# alim_2016.net
KiCad netlist of a schematic drawn in EAGLE
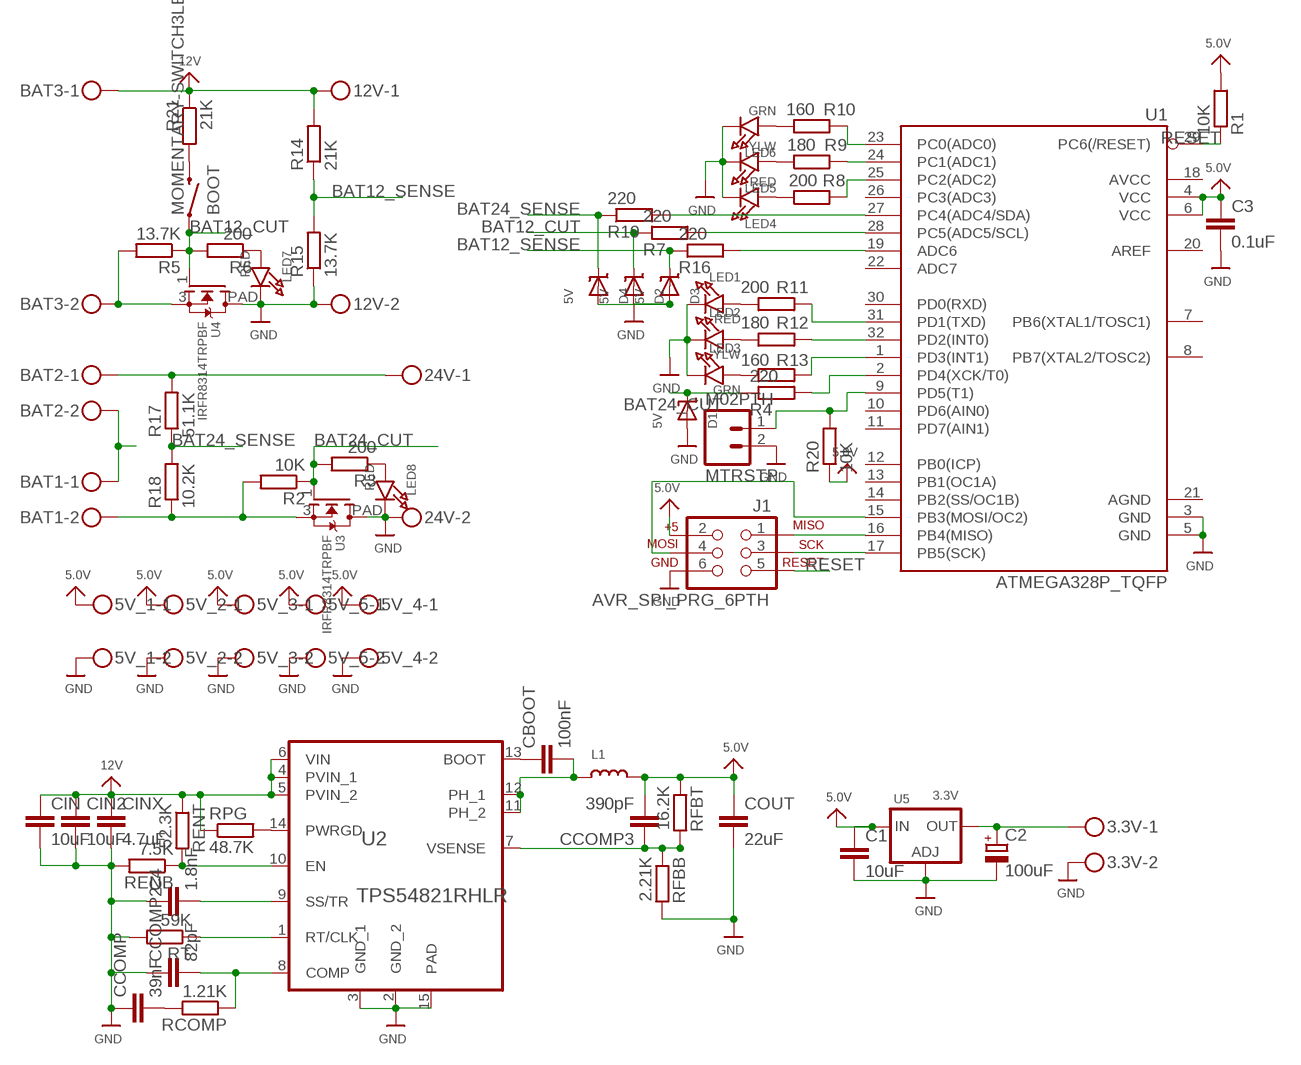
[diagram p0: schematic, sheet 1]

(export (version "E")
  (design (tool "Eeschema 10.0.6"))
  (components
    (comp (ref "3.3V")
      (value "WURTH_2PIN311")
      (footprint "eagle-import:WURTH311")
      (libsource (lib "eagle-import") (part "WURTH_2PIN311"))
    )
    (comp (ref "5V_1")
      (value "WURTH_2PIN311")
      (footprint "eagle-import:WURTH311")
      (libsource (lib "eagle-import") (part "WURTH_2PIN311"))
    )
    (comp (ref "5V_2")
      (value "WURTH_2PIN311")
      (footprint "eagle-import:WURTH311")
      (libsource (lib "eagle-import") (part "WURTH_2PIN311"))
    )
    (comp (ref "5V_3")
      (value "WURTH_2PIN311")
      (footprint "eagle-import:WURTH311")
      (libsource (lib "eagle-import") (part "WURTH_2PIN311"))
    )
    (comp (ref "5V_4")
      (value "WURTH_2PIN311")
      (footprint "eagle-import:WURTH311")
      (libsource (lib "eagle-import") (part "WURTH_2PIN311"))
    )
    (comp (ref "5V_5")
      (value "WURTH_2PIN311")
      (footprint "eagle-import:WURTH311")
      (libsource (lib "eagle-import") (part "WURTH_2PIN311"))
    )
    (comp (ref "12V")
      (value "WURTH_2PIN311")
      (footprint "eagle-import:WURTH311")
      (libsource (lib "eagle-import") (part "WURTH_2PIN311"))
    )
    (comp (ref "24V")
      (value "WURTH_2PIN311")
      (footprint "eagle-import:WURTH311")
      (libsource (lib "eagle-import") (part "WURTH_2PIN311"))
    )
    (comp (ref "BAT1")
      (value "WURTH_2PIN313")
      (footprint "eagle-import:WURTH313_2")
      (libsource (lib "eagle-import") (part "WURTH_2PIN313"))
    )
    (comp (ref "BAT2")
      (value "WURTH_2PIN313")
      (footprint "eagle-import:WURTH313_2")
      (libsource (lib "eagle-import") (part "WURTH_2PIN313"))
    )
    (comp (ref "BAT3")
      (value "WURTH_2PIN313")
      (footprint "eagle-import:WURTH313_2")
      (libsource (lib "eagle-import") (part "WURTH_2PIN313"))
    )
    (comp (ref "BOOT")
      (value "MOMENTARY-SWITCH3LEG")
      (footprint "eagle-import:3LEGGED-TACT")
      (libsource (lib "eagle-import") (part "MOMENTARY-SWITCH3LEG"))
    )
    (comp (ref "C1")
      (value "10uF")
      (footprint "eagle-import:C0805")
      (libsource (lib "eagle-import") (part "C-EUC0805"))
    )
    (comp (ref "C2")
      (value "100uF")
      (footprint "eagle-import:E2,5-7")
      (libsource (lib "eagle-import") (part "CPOL-EUE2.5-7"))
    )
    (comp (ref "C3")
      (value "0.1uF")
      (footprint "eagle-import:C0805")
      (libsource (lib "eagle-import") (part "C-EUC0805"))
    )
    (comp (ref "C4")
      (value "1.8nF")
      (footprint "eagle-import:C0805")
      (libsource (lib "eagle-import") (part "C-EUC0805"))
    )
    (comp (ref "CBOOT")
      (value "100nF")
      (footprint "eagle-import:C0805")
      (libsource (lib "eagle-import") (part "C-EUC0805"))
    )
    (comp (ref "CCOMP")
      (value "39nF")
      (footprint "eagle-import:C0805")
      (libsource (lib "eagle-import") (part "C-EUC0805"))
    )
    (comp (ref "CCOMP2")
      (value "82pF")
      (footprint "eagle-import:C0805")
      (libsource (lib "eagle-import") (part "C-EUC0805"))
    )
    (comp (ref "CCOMP3")
      (value "390pF")
      (footprint "eagle-import:C0805")
      (libsource (lib "eagle-import") (part "C-EUC0805"))
    )
    (comp (ref "CIN")
      (value "10uF")
      (footprint "eagle-import:C0805")
      (libsource (lib "eagle-import") (part "C-EUC0805"))
    )
    (comp (ref "CIN2")
      (value "10uF")
      (footprint "eagle-import:C0805")
      (libsource (lib "eagle-import") (part "C-EUC0805"))
    )
    (comp (ref "CINX")
      (value "4.7uF")
      (footprint "eagle-import:C0805")
      (libsource (lib "eagle-import") (part "C-EUC0805"))
    )
    (comp (ref "COUT")
      (value "22uF")
      (footprint "eagle-import:C0805")
      (libsource (lib "eagle-import") (part "C-EUC0805"))
    )
    (comp (ref "D1")
      (value "5V")
      (footprint "eagle-import:SOD-123")
      (libsource (lib "eagle-import") (part "DIODE-ZENERSOD123"))
    )
    (comp (ref "D2")
      (value "5V")
      (footprint "eagle-import:SOD-123")
      (libsource (lib "eagle-import") (part "DIODE-ZENERSOD123"))
    )
    (comp (ref "D3")
      (value "5V")
      (footprint "eagle-import:SOD-123")
      (libsource (lib "eagle-import") (part "DIODE-ZENERSOD123"))
    )
    (comp (ref "D4")
      (value "5V")
      (footprint "eagle-import:SOD-123")
      (libsource (lib "eagle-import") (part "DIODE-ZENERSOD123"))
    )
    (comp (ref "J1")
      (value "AVR_SPI_PRG_6PTH")
      (footprint "eagle-import:2X3")
      (libsource (lib "eagle-import") (part "AVR_SPI_PRG_6PTH"))
    )
    (comp (ref "L1")
      (value "2.2uH")
      (footprint "eagle-import:XAL5030")
      (libsource (lib "eagle-import") (part "XAL5030"))
    )
    (comp (ref "LED1")
      (value "RED")
      (footprint "eagle-import:CHIPLED_0805_NOOUTLINE")
      (libsource (lib "eagle-import") (part "LED0805_NOOUTLINE"))
    )
    (comp (ref "LED2")
      (value "YLW")
      (footprint "eagle-import:CHIPLED_0805_NOOUTLINE")
      (libsource (lib "eagle-import") (part "LED0805_NOOUTLINE"))
    )
    (comp (ref "LED3")
      (value "GRN")
      (footprint "eagle-import:CHIPLED_0805_NOOUTLINE")
      (libsource (lib "eagle-import") (part "LED0805_NOOUTLINE"))
    )
    (comp (ref "LED4")
      (value "RED")
      (footprint "eagle-import:CHIPLED_0805_NOOUTLINE")
      (libsource (lib "eagle-import") (part "LED0805_NOOUTLINE"))
    )
    (comp (ref "LED5")
      (value "YLW")
      (footprint "eagle-import:CHIPLED_0805_NOOUTLINE")
      (libsource (lib "eagle-import") (part "LED0805_NOOUTLINE"))
    )
    (comp (ref "LED6")
      (value "GRN")
      (footprint "eagle-import:CHIPLED_0805_NOOUTLINE")
      (libsource (lib "eagle-import") (part "LED0805_NOOUTLINE"))
    )
    (comp (ref "LED7")
      (value "RED")
      (footprint "eagle-import:CHIPLED_0805_NOOUTLINE")
      (libsource (lib "eagle-import") (part "LED0805_NOOUTLINE"))
    )
    (comp (ref "LED8")
      (value "RED")
      (footprint "eagle-import:CHIPLED_0805_NOOUTLINE")
      (libsource (lib "eagle-import") (part "LED0805_NOOUTLINE"))
    )
    (comp (ref "MTRSTP")
      (value "M02PTH")
      (footprint "eagle-import:1X02")
      (libsource (lib "eagle-import") (part "M02PTH"))
    )
    (comp (ref "R1")
      (value "10K")
      (footprint "eagle-import:M0805")
      (libsource (lib "eagle-import") (part "R-EU_M0805"))
    )
    (comp (ref "R2")
      (value "10K")
      (footprint "eagle-import:M0805")
      (libsource (lib "eagle-import") (part "R-EU_M0805"))
    )
    (comp (ref "R3")
      (value "200")
      (footprint "eagle-import:M0805")
      (libsource (lib "eagle-import") (part "R-EU_M0805"))
    )
    (comp (ref "R4")
      (value "220")
      (footprint "eagle-import:M0805")
      (libsource (lib "eagle-import") (part "R-EU_M0805"))
    )
    (comp (ref "R5")
      (value "13.7K")
      (footprint "eagle-import:M0805")
      (libsource (lib "eagle-import") (part "R-EU_M0805"))
    )
    (comp (ref "R6")
      (value "200")
      (footprint "eagle-import:M0805")
      (libsource (lib "eagle-import") (part "R-EU_M0805"))
    )
    (comp (ref "R7")
      (value "220")
      (footprint "eagle-import:M0805")
      (libsource (lib "eagle-import") (part "R-EU_M0805"))
    )
    (comp (ref "R8")
      (value "200")
      (footprint "eagle-import:M0805")
      (libsource (lib "eagle-import") (part "R-EU_M0805"))
    )
    (comp (ref "R9")
      (value "180")
      (footprint "eagle-import:M0805")
      (libsource (lib "eagle-import") (part "R-EU_M0805"))
    )
    (comp (ref "R10")
      (value "160")
      (footprint "eagle-import:M0805")
      (libsource (lib "eagle-import") (part "R-EU_M0805"))
    )
    (comp (ref "R11")
      (value "200")
      (footprint "eagle-import:M0805")
      (libsource (lib "eagle-import") (part "R-EU_M0805"))
    )
    (comp (ref "R12")
      (value "180")
      (footprint "eagle-import:M0805")
      (libsource (lib "eagle-import") (part "R-EU_M0805"))
    )
    (comp (ref "R13")
      (value "160")
      (footprint "eagle-import:M0805")
      (libsource (lib "eagle-import") (part "R-EU_M0805"))
    )
    (comp (ref "R14")
      (value "21K")
      (footprint "eagle-import:M0805")
      (libsource (lib "eagle-import") (part "R-EU_M0805"))
    )
    (comp (ref "R15")
      (value "13.7K")
      (footprint "eagle-import:M0805")
      (libsource (lib "eagle-import") (part "R-EU_M0805"))
    )
    (comp (ref "R16")
      (value "220")
      (footprint "eagle-import:M0805")
      (libsource (lib "eagle-import") (part "R-EU_M0805"))
    )
    (comp (ref "R17")
      (value "51.1K")
      (footprint "eagle-import:M0805")
      (libsource (lib "eagle-import") (part "R-EU_M0805"))
    )
    (comp (ref "R18")
      (value "10.2K")
      (footprint "eagle-import:M0805")
      (libsource (lib "eagle-import") (part "R-EU_M0805"))
    )
    (comp (ref "R19")
      (value "220")
      (footprint "eagle-import:M0805")
      (libsource (lib "eagle-import") (part "R-EU_M0805"))
    )
    (comp (ref "R20")
      (value "10K")
      (footprint "eagle-import:M0805")
      (libsource (lib "eagle-import") (part "R-EU_M0805"))
    )
    (comp (ref "R21")
      (value "21K")
      (footprint "eagle-import:M0805")
      (libsource (lib "eagle-import") (part "R-EU_M0805"))
    )
    (comp (ref "RCOMP")
      (value "1.21K")
      (footprint "eagle-import:M0805")
      (libsource (lib "eagle-import") (part "R-EU_M0805"))
    )
    (comp (ref "RENB")
      (value "7.5K")
      (footprint "eagle-import:M0805")
      (libsource (lib "eagle-import") (part "R-EU_M0805"))
    )
    (comp (ref "RENT")
      (value "52.3K")
      (footprint "eagle-import:M0805")
      (libsource (lib "eagle-import") (part "R-EU_M0805"))
    )
    (comp (ref "RFBB")
      (value "2.21K")
      (footprint "eagle-import:M0805")
      (libsource (lib "eagle-import") (part "R-EU_M0805"))
    )
    (comp (ref "RFBT")
      (value "16.2K")
      (footprint "eagle-import:M0805")
      (libsource (lib "eagle-import") (part "R-EU_M0805"))
    )
    (comp (ref "RPG")
      (value "48.7K")
      (footprint "eagle-import:M0805")
      (libsource (lib "eagle-import") (part "R-EU_M0805"))
    )
    (comp (ref "RT")
      (value "59K")
      (footprint "eagle-import:M0805")
      (libsource (lib "eagle-import") (part "R-EU_M0805"))
    )
    (comp (ref "U1")
      (value "ATMEGA328P_TQFP")
      (footprint "eagle-import:TQFP32-08")
      (libsource (lib "eagle-import") (part "ATMEGA328P_TQFP"))
    )
    (comp (ref "U2")
      (value "TPS54821RHLR")
      (footprint "eagle-import:S-PVQFN-N14")
      (libsource (lib "eagle-import") (part "TPS54821RHLR"))
    )
    (comp (ref "U3")
      (value "IRFR8314TRPBF")
      (footprint "eagle-import:DPACK_1")
      (libsource (lib "eagle-import") (part "IRFR8314TRPBF"))
    )
    (comp (ref "U4")
      (value "IRFR8314TRPBF")
      (footprint "eagle-import:DPACK_1")
      (libsource (lib "eagle-import") (part "IRFR8314TRPBF"))
    )
    (comp (ref "U5")
      (value "3.3V")
      (footprint "eagle-import:TO252")
      (libsource (lib "eagle-import") (part "LM1117TO252"))
    )
  )
  (nets
    (net (code "1") (name "/BAT12_CUT") (class "Default")
      (node (ref "BOOT") (pin "1") (pinfunction "1_1") (pintype "passive"))
      (node (ref "D2") (pin "C") (pinfunction "C_C") (pintype "passive"))
      (node (ref "R5") (pin "1") (pinfunction "1_1") (pintype "passive"))
      (node (ref "R6") (pin "2") (pinfunction "2_2") (pintype "passive"))
      (node (ref "R7") (pin "1") (pinfunction "1_1") (pintype "passive"))
      (node (ref "U4") (pin "1") (pinfunction "G_1") (pintype "bidirectional"))
    )
    (net (code "2") (name "/BAT12_SENSE") (class "Default")
      (node (ref "D3") (pin "C") (pinfunction "C_C") (pintype "passive"))
      (node (ref "R14") (pin "1") (pinfunction "1_1") (pintype "passive"))
      (node (ref "R15") (pin "2") (pinfunction "2_2") (pintype "passive"))
      (node (ref "R16") (pin "1") (pinfunction "1_1") (pintype "passive"))
    )
    (net (code "3") (name "/BAT24_CUT") (class "Default")
      (node (ref "D1") (pin "C") (pinfunction "C_C") (pintype "passive"))
      (node (ref "R2") (pin "1") (pinfunction "1_1") (pintype "passive"))
      (node (ref "R3") (pin "2") (pinfunction "2_2") (pintype "passive"))
      (node (ref "R4") (pin "1") (pinfunction "1_1") (pintype "passive"))
      (node (ref "U3") (pin "1") (pinfunction "G_1") (pintype "bidirectional"))
    )
    (net (code "4") (name "/BAT24_SENSE") (class "Default")
      (node (ref "D4") (pin "C") (pinfunction "C_C") (pintype "passive"))
      (node (ref "R17") (pin "1") (pinfunction "1_1") (pintype "passive"))
      (node (ref "R18") (pin "2") (pinfunction "2_2") (pintype "passive"))
      (node (ref "R19") (pin "1") (pinfunction "1_1") (pintype "passive"))
    )
    (net (code "5") (name "/RESET") (class "Default")
      (node (ref "J1") (pin "5") (pinfunction "5_5") (pintype "passive"))
      (node (ref "R1") (pin "1") (pinfunction "1_1") (pintype "passive"))
      (node (ref "U1") (pin "29") (pinfunction "PC6(/RESET)_29") (pintype "bidirectional"))
    )
    (net (code "6") (name "5.0V") (class "Default")
      (node (ref "5V_1") (pin "P$1") (pinfunction "KL_P$1") (pintype "power_in"))
      (node (ref "5V_2") (pin "P$1") (pinfunction "KL_P$1") (pintype "power_in"))
      (node (ref "5V_3") (pin "P$1") (pinfunction "KL_P$1") (pintype "power_in"))
      (node (ref "5V_4") (pin "P$1") (pinfunction "KL_P$1") (pintype "power_in"))
      (node (ref "5V_5") (pin "P$1") (pinfunction "KL_P$1") (pintype "power_in"))
      (node (ref "C1") (pin "1") (pinfunction "1_1") (pintype "passive"))
      (node (ref "C3") (pin "1") (pinfunction "1_1") (pintype "passive"))
      (node (ref "CCOMP3") (pin "2") (pinfunction "2_2") (pintype "passive"))
      (node (ref "COUT") (pin "1") (pinfunction "1_1") (pintype "passive"))
      (node (ref "J1") (pin "2") (pinfunction "2_2") (pintype "passive"))
      (node (ref "L1") (pin "2") (pinfunction "2_2") (pintype "passive"))
      (node (ref "R1") (pin "2") (pinfunction "2_2") (pintype "passive"))
      (node (ref "R20") (pin "1") (pinfunction "1_1") (pintype "passive"))
      (node (ref "RFBT") (pin "1") (pinfunction "1_1") (pintype "passive"))
      (node (ref "U1") (pin "4") (pinfunction "VCC_4") (pintype "bidirectional"))
      (node (ref "U1") (pin "6") (pinfunction "VCC_6") (pintype "bidirectional"))
      (node (ref "U5") (pin "2") (pinfunction "IN_2") (pintype "input"))
    )
    (net (code "7") (name "12V") (class "Default")
      (node (ref "12V") (pin "P$1") (pinfunction "KL_P$1") (pintype "power_in"))
      (node (ref "BAT3") (pin "P$1") (pinfunction "KL_P$1") (pintype "power_in"))
      (node (ref "CIN") (pin "1") (pinfunction "1_1") (pintype "passive"))
      (node (ref "CIN2") (pin "1") (pinfunction "1_1") (pintype "passive"))
      (node (ref "CINX") (pin "1") (pinfunction "1_1") (pintype "passive"))
      (node (ref "R14") (pin "2") (pinfunction "2_2") (pintype "passive"))
      (node (ref "R21") (pin "1") (pinfunction "1_1") (pintype "passive"))
      (node (ref "RENT") (pin "1") (pinfunction "1_1") (pintype "passive"))
      (node (ref "RPG") (pin "1") (pinfunction "1_1") (pintype "passive"))
      (node (ref "U2") (pin "4") (pinfunction "PVIN_1_4") (pintype "passive"))
      (node (ref "U2") (pin "5") (pinfunction "PVIN_2_5") (pintype "passive"))
      (node (ref "U2") (pin "6") (pinfunction "VIN_6") (pintype "passive"))
    )
    (net (code "8") (name "GND") (class "Default")
      (node (ref "12V") (pin "P$2") (pinfunction "KL_P$2") (pintype "power_in"))
      (node (ref "24V") (pin "P$2") (pinfunction "KL_P$2") (pintype "power_in"))
      (node (ref "3.3V") (pin "P$2") (pinfunction "KL_P$2") (pintype "power_in"))
      (node (ref "5V_1") (pin "P$2") (pinfunction "KL_P$2") (pintype "power_in"))
      (node (ref "5V_2") (pin "P$2") (pinfunction "KL_P$2") (pintype "power_in"))
      (node (ref "5V_3") (pin "P$2") (pinfunction "KL_P$2") (pintype "power_in"))
      (node (ref "5V_4") (pin "P$2") (pinfunction "KL_P$2") (pintype "power_in"))
      (node (ref "5V_5") (pin "P$2") (pinfunction "KL_P$2") (pintype "power_in"))
      (node (ref "C1") (pin "2") (pinfunction "2_2") (pintype "passive"))
      (node (ref "C2") (pin "-") (pinfunction "-_-") (pintype "passive"))
      (node (ref "C3") (pin "2") (pinfunction "2_2") (pintype "passive"))
      (node (ref "C4") (pin "1") (pinfunction "1_1") (pintype "passive"))
      (node (ref "CCOMP") (pin "1") (pinfunction "1_1") (pintype "passive"))
      (node (ref "CCOMP2") (pin "1") (pinfunction "1_1") (pintype "passive"))
      (node (ref "CIN") (pin "2") (pinfunction "2_2") (pintype "passive"))
      (node (ref "CIN2") (pin "2") (pinfunction "2_2") (pintype "passive"))
      (node (ref "CINX") (pin "2") (pinfunction "2_2") (pintype "passive"))
      (node (ref "COUT") (pin "2") (pinfunction "2_2") (pintype "passive"))
      (node (ref "D1") (pin "A") (pinfunction "A_A") (pintype "passive"))
      (node (ref "D2") (pin "A") (pinfunction "A_A") (pintype "passive"))
      (node (ref "D3") (pin "A") (pinfunction "A_A") (pintype "passive"))
      (node (ref "D4") (pin "A") (pinfunction "A_A") (pintype "passive"))
      (node (ref "J1") (pin "6") (pinfunction "6_6") (pintype "passive"))
      (node (ref "LED1") (pin "C") (pinfunction "C_C") (pintype "passive"))
      (node (ref "LED2") (pin "C") (pinfunction "C_C") (pintype "passive"))
      (node (ref "LED3") (pin "C") (pinfunction "C_C") (pintype "passive"))
      (node (ref "LED4") (pin "C") (pinfunction "C_C") (pintype "passive"))
      (node (ref "LED5") (pin "C") (pinfunction "C_C") (pintype "passive"))
      (node (ref "LED6") (pin "C") (pinfunction "C_C") (pintype "passive"))
      (node (ref "LED7") (pin "C") (pinfunction "C_C") (pintype "passive"))
      (node (ref "LED8") (pin "C") (pinfunction "C_C") (pintype "passive"))
      (node (ref "MTRSTP") (pin "2") (pinfunction "2_2") (pintype "passive"))
      (node (ref "R15") (pin "1") (pinfunction "1_1") (pintype "passive"))
      (node (ref "RENB") (pin "2") (pinfunction "2_2") (pintype "passive"))
      (node (ref "RFBB") (pin "2") (pinfunction "2_2") (pintype "passive"))
      (node (ref "RT") (pin "2") (pinfunction "2_2") (pintype "passive"))
      (node (ref "U1") (pin "3") (pinfunction "GND_3") (pintype "bidirectional"))
      (node (ref "U1") (pin "5") (pinfunction "GND_5") (pintype "bidirectional"))
      (node (ref "U2") (pin "15") (pinfunction "PAD_15") (pintype "passive"))
      (node (ref "U2") (pin "2") (pinfunction "GND_2_2") (pintype "passive"))
      (node (ref "U2") (pin "3") (pinfunction "GND_1_3") (pintype "passive"))
      (node (ref "U3") (pin "PAD") (pinfunction "D_PAD") (pintype "bidirectional"))
      (node (ref "U4") (pin "PAD") (pinfunction "D_PAD") (pintype "bidirectional"))
      (node (ref "U5") (pin "1") (pinfunction "ADJ_1") (pintype "input"))
    )
    (net (code "9") (name "Net-(3.3VA-KL)") (class "Default")
      (node (ref "3.3V") (pin "P$1") (pinfunction "KL_P$1") (pintype "power_in"))
      (node (ref "C2") (pin "+") (pinfunction "+_+") (pintype "passive"))
      (node (ref "U5") (pin "3") (pinfunction "OUT_3") (pintype "passive"))
    )
    (net (code "10") (name "Net-(24VA-KL)") (class "Default")
      (node (ref "24V") (pin "P$1") (pinfunction "KL_P$1") (pintype "power_in"))
      (node (ref "BAT2") (pin "P$1") (pinfunction "KL_P$1") (pintype "power_in"))
      (node (ref "R17") (pin "2") (pinfunction "2_2") (pintype "passive"))
    )
    (net (code "11") (name "Net-(BAT1A-KL)") (class "Default")
      (node (ref "BAT1") (pin "P$1") (pinfunction "KL_P$1") (pintype "power_in"))
      (node (ref "BAT2") (pin "P$2") (pinfunction "KL_P$2") (pintype "power_in"))
    )
    (net (code "12") (name "Net-(BAT1B-KL)") (class "Default")
      (node (ref "BAT1") (pin "P$2") (pinfunction "KL_P$2") (pintype "power_in"))
      (node (ref "R18") (pin "1") (pinfunction "1_1") (pintype "passive"))
      (node (ref "R2") (pin "2") (pinfunction "2_2") (pintype "passive"))
      (node (ref "U3") (pin "3") (pinfunction "S_3") (pintype "bidirectional"))
    )
    (net (code "13") (name "Net-(BAT3B-KL)") (class "Default")
      (node (ref "BAT3") (pin "P$2") (pinfunction "KL_P$2") (pintype "power_in"))
      (node (ref "R5") (pin "2") (pinfunction "2_2") (pintype "passive"))
      (node (ref "U4") (pin "3") (pinfunction "S_3") (pintype "bidirectional"))
    )
    (net (code "14") (name "Net-(BOOT-2)") (class "Default")
      (node (ref "BOOT") (pin "3") (pinfunction "2_3") (pintype "passive"))
      (node (ref "R21") (pin "2") (pinfunction "2_2") (pintype "passive"))
    )
    (net (code "15") (name "Net-(CCOMP-Pad2)") (class "Default")
      (node (ref "CCOMP") (pin "2") (pinfunction "2_2") (pintype "passive"))
      (node (ref "RCOMP") (pin "2") (pinfunction "2_2") (pintype "passive"))
    )
    (net (code "16") (name "Net-(LED1-PadA)") (class "Default")
      (node (ref "LED1") (pin "A") (pinfunction "A_A") (pintype "passive"))
      (node (ref "R11") (pin "1") (pinfunction "1_1") (pintype "passive"))
    )
    (net (code "17") (name "Net-(LED2-PadA)") (class "Default")
      (node (ref "LED2") (pin "A") (pinfunction "A_A") (pintype "passive"))
      (node (ref "R12") (pin "1") (pinfunction "1_1") (pintype "passive"))
    )
    (net (code "18") (name "Net-(LED3-PadA)") (class "Default")
      (node (ref "LED3") (pin "A") (pinfunction "A_A") (pintype "passive"))
      (node (ref "R13") (pin "1") (pinfunction "1_1") (pintype "passive"))
    )
    (net (code "19") (name "Net-(LED4-PadA)") (class "Default")
      (node (ref "LED4") (pin "A") (pinfunction "A_A") (pintype "passive"))
      (node (ref "R8") (pin "1") (pinfunction "1_1") (pintype "passive"))
    )
    (net (code "20") (name "Net-(LED5-PadA)") (class "Default")
      (node (ref "LED5") (pin "A") (pinfunction "A_A") (pintype "passive"))
      (node (ref "R9") (pin "1") (pinfunction "1_1") (pintype "passive"))
    )
    (net (code "21") (name "Net-(LED6-PadA)") (class "Default")
      (node (ref "LED6") (pin "A") (pinfunction "A_A") (pintype "passive"))
      (node (ref "R10") (pin "1") (pinfunction "1_1") (pintype "passive"))
    )
    (net (code "22") (name "Net-(LED7-PadA)") (class "Default")
      (node (ref "LED7") (pin "A") (pinfunction "A_A") (pintype "passive"))
      (node (ref "R6") (pin "1") (pinfunction "1_1") (pintype "passive"))
    )
    (net (code "23") (name "Net-(LED8-PadA)") (class "Default")
      (node (ref "LED8") (pin "A") (pinfunction "A_A") (pintype "passive"))
      (node (ref "R3") (pin "1") (pinfunction "1_1") (pintype "passive"))
    )
    (net (code "24") (name "Net-(U1-ADC6)") (class "Default")
      (node (ref "R16") (pin "2") (pinfunction "2_2") (pintype "passive"))
      (node (ref "U1") (pin "19") (pinfunction "ADC6_19") (pintype "bidirectional"))
    )
    (net (code "25") (name "Net-(U1-PB3(MOSI{slash}OC2))") (class "Default")
      (node (ref "J1") (pin "4") (pinfunction "4_4") (pintype "passive"))
      (node (ref "U1") (pin "15") (pinfunction "PB3(MOSI/OC2)_15") (pintype "bidirectional"))
    )
    (net (code "26") (name "Net-(U1-PB4(MISO))") (class "Default")
      (node (ref "J1") (pin "1") (pinfunction "1_1") (pintype "passive"))
      (node (ref "U1") (pin "16") (pinfunction "PB4(MISO)_16") (pintype "bidirectional"))
    )
    (net (code "27") (name "Net-(U1-PB5(SCK))") (class "Default")
      (node (ref "J1") (pin "3") (pinfunction "3_3") (pintype "passive"))
      (node (ref "U1") (pin "17") (pinfunction "PB5(SCK)_17") (pintype "bidirectional"))
    )
    (net (code "28") (name "Net-(U1-PC0(ADC0))") (class "Default")
      (node (ref "R10") (pin "2") (pinfunction "2_2") (pintype "passive"))
      (node (ref "U1") (pin "23") (pinfunction "PC0(ADC0)_23") (pintype "bidirectional"))
    )
    (net (code "29") (name "Net-(U1-PC1(ADC1))") (class "Default")
      (node (ref "R9") (pin "2") (pinfunction "2_2") (pintype "passive"))
      (node (ref "U1") (pin "24") (pinfunction "PC1(ADC1)_24") (pintype "bidirectional"))
    )
    (net (code "30") (name "Net-(U1-PC2(ADC2))") (class "Default")
      (node (ref "R8") (pin "2") (pinfunction "2_2") (pintype "passive"))
      (node (ref "U1") (pin "25") (pinfunction "PC2(ADC2)_25") (pintype "bidirectional"))
    )
    (net (code "31") (name "Net-(U1-PC4(ADC4{slash}SDA))") (class "Default")
      (node (ref "R19") (pin "2") (pinfunction "2_2") (pintype "passive"))
      (node (ref "U1") (pin "27") (pinfunction "PC4(ADC4/SDA)_27") (pintype "bidirectional"))
    )
    (net (code "32") (name "Net-(U1-PC5(ADC5{slash}SCL))") (class "Default")
      (node (ref "R7") (pin "2") (pinfunction "2_2") (pintype "passive"))
      (node (ref "U1") (pin "28") (pinfunction "PC5(ADC5/SCL)_28") (pintype "bidirectional"))
    )
    (net (code "33") (name "Net-(U1-PD1(TXD))") (class "Default")
      (node (ref "R11") (pin "2") (pinfunction "2_2") (pintype "passive"))
      (node (ref "U1") (pin "31") (pinfunction "PD1(TXD)_31") (pintype "bidirectional"))
    )
    (net (code "34") (name "Net-(U1-PD2(INT0))") (class "Default")
      (node (ref "R12") (pin "2") (pinfunction "2_2") (pintype "passive"))
      (node (ref "U1") (pin "32") (pinfunction "PD2(INT0)_32") (pintype "bidirectional"))
    )
    (net (code "35") (name "Net-(U1-PD3(INT1))") (class "Default")
      (node (ref "R13") (pin "2") (pinfunction "2_2") (pintype "passive"))
      (node (ref "U1") (pin "1") (pinfunction "PD3(INT1)_1") (pintype "bidirectional"))
    )
    (net (code "36") (name "Net-(U1-PD4(XCK{slash}T0))") (class "Default")
      (node (ref "R4") (pin "2") (pinfunction "2_2") (pintype "passive"))
      (node (ref "U1") (pin "2") (pinfunction "PD4(XCK/T0)_2") (pintype "bidirectional"))
    )
    (net (code "37") (name "Net-(U1-PD5(T1))") (class "Default")
      (node (ref "MTRSTP") (pin "1") (pinfunction "1_1") (pintype "passive"))
      (node (ref "R20") (pin "2") (pinfunction "2_2") (pintype "passive"))
      (node (ref "U1") (pin "9") (pinfunction "PD5(T1)_9") (pintype "bidirectional"))
    )
    (net (code "38") (name "Net-(U2-BOOT)") (class "Default")
      (node (ref "CBOOT") (pin "1") (pinfunction "1_1") (pintype "passive"))
      (node (ref "U2") (pin "13") (pinfunction "BOOT_13") (pintype "passive"))
    )
    (net (code "39") (name "Net-(U2-COMP)") (class "Default")
      (node (ref "CCOMP2") (pin "2") (pinfunction "2_2") (pintype "passive"))
      (node (ref "RCOMP") (pin "1") (pinfunction "1_1") (pintype "passive"))
      (node (ref "U2") (pin "8") (pinfunction "COMP_8") (pintype "passive"))
    )
    (net (code "40") (name "Net-(U2-EN)") (class "Default")
      (node (ref "RENB") (pin "1") (pinfunction "1_1") (pintype "passive"))
      (node (ref "RENT") (pin "2") (pinfunction "2_2") (pintype "passive"))
      (node (ref "U2") (pin "10") (pinfunction "EN_10") (pintype "passive"))
    )
    (net (code "41") (name "Net-(U2-PH_1)") (class "Default")
      (node (ref "CBOOT") (pin "2") (pinfunction "2_2") (pintype "passive"))
      (node (ref "L1") (pin "1") (pinfunction "1_1") (pintype "passive"))
      (node (ref "U2") (pin "11") (pinfunction "PH_2_11") (pintype "passive"))
      (node (ref "U2") (pin "12") (pinfunction "PH_1_12") (pintype "passive"))
    )
    (net (code "42") (name "Net-(U2-PWRGD)") (class "Default")
      (node (ref "RPG") (pin "2") (pinfunction "2_2") (pintype "passive"))
      (node (ref "U2") (pin "14") (pinfunction "PWRGD_14") (pintype "passive"))
    )
    (net (code "43") (name "Net-(U2-RT{slash}CLK)") (class "Default")
      (node (ref "RT") (pin "1") (pinfunction "1_1") (pintype "passive"))
      (node (ref "U2") (pin "1") (pinfunction "RT/CLK_1") (pintype "passive"))
    )
    (net (code "44") (name "Net-(U2-SS{slash}TR)") (class "Default")
      (node (ref "C4") (pin "2") (pinfunction "2_2") (pintype "passive"))
      (node (ref "U2") (pin "9") (pinfunction "SS/TR_9") (pintype "passive"))
    )
    (net (code "45") (name "Net-(U2-VSENSE)") (class "Default")
      (node (ref "CCOMP3") (pin "1") (pinfunction "1_1") (pintype "passive"))
      (node (ref "RFBB") (pin "1") (pinfunction "1_1") (pintype "passive"))
      (node (ref "RFBT") (pin "2") (pinfunction "2_2") (pintype "passive"))
      (node (ref "U2") (pin "7") (pinfunction "VSENSE_7") (pintype "passive"))
    )
    (net (code "46") (name "unconnected-(U1-ADC7-Pad22)") (class "Default")
      (node (ref "U1") (pin "22") (pinfunction "ADC7_22") (pintype "bidirectional"))
    )
    (net (code "47") (name "unconnected-(U1-AGND-Pad21)") (class "Default")
      (node (ref "U1") (pin "21") (pinfunction "AGND_21") (pintype "bidirectional"))
    )
    (net (code "48") (name "unconnected-(U1-AREF-Pad20)") (class "Default")
      (node (ref "U1") (pin "20") (pinfunction "AREF_20") (pintype "bidirectional"))
    )
    (net (code "49") (name "unconnected-(U1-AVCC-Pad18)") (class "Default")
      (node (ref "U1") (pin "18") (pinfunction "AVCC_18") (pintype "bidirectional"))
    )
    (net (code "50") (name "unconnected-(U1-PB0(ICP)-Pad12)") (class "Default")
      (node (ref "U1") (pin "12") (pinfunction "PB0(ICP)_12") (pintype "bidirectional"))
    )
    (net (code "51") (name "unconnected-(U1-PB1(OC1A)-Pad13)") (class "Default")
      (node (ref "U1") (pin "13") (pinfunction "PB1(OC1A)_13") (pintype "bidirectional"))
    )
    (net (code "52") (name "unconnected-(U1-PB2(SS{slash}OC1B)-Pad14)") (class "Default")
      (node (ref "U1") (pin "14") (pinfunction "PB2(SS/OC1B)_14") (pintype "bidirectional"))
    )
    (net (code "53") (name "unconnected-(U1-PB6(XTAL1{slash}TOSC1)-Pad7)") (class "Default")
      (node (ref "U1") (pin "7") (pinfunction "PB6(XTAL1/TOSC1)_7") (pintype "bidirectional"))
    )
    (net (code "54") (name "unconnected-(U1-PB7(XTAL2{slash}TOSC2)-Pad8)") (class "Default")
      (node (ref "U1") (pin "8") (pinfunction "PB7(XTAL2/TOSC2)_8") (pintype "bidirectional"))
    )
    (net (code "55") (name "unconnected-(U1-PC3(ADC3)-Pad26)") (class "Default")
      (node (ref "U1") (pin "26") (pinfunction "PC3(ADC3)_26") (pintype "bidirectional"))
    )
    (net (code "56") (name "unconnected-(U1-PD0(RXD)-Pad30)") (class "Default")
      (node (ref "U1") (pin "30") (pinfunction "PD0(RXD)_30") (pintype "bidirectional"))
    )
    (net (code "57") (name "unconnected-(U1-PD6(AIN0)-Pad10)") (class "Default")
      (node (ref "U1") (pin "10") (pinfunction "PD6(AIN0)_10") (pintype "bidirectional"))
    )
    (net (code "58") (name "unconnected-(U1-PD7(AIN1)-Pad11)") (class "Default")
      (node (ref "U1") (pin "11") (pinfunction "PD7(AIN1)_11") (pintype "bidirectional"))
    )
  )
)
